# acadam.net
KiCad netlist of a schematic drawn in EAGLE
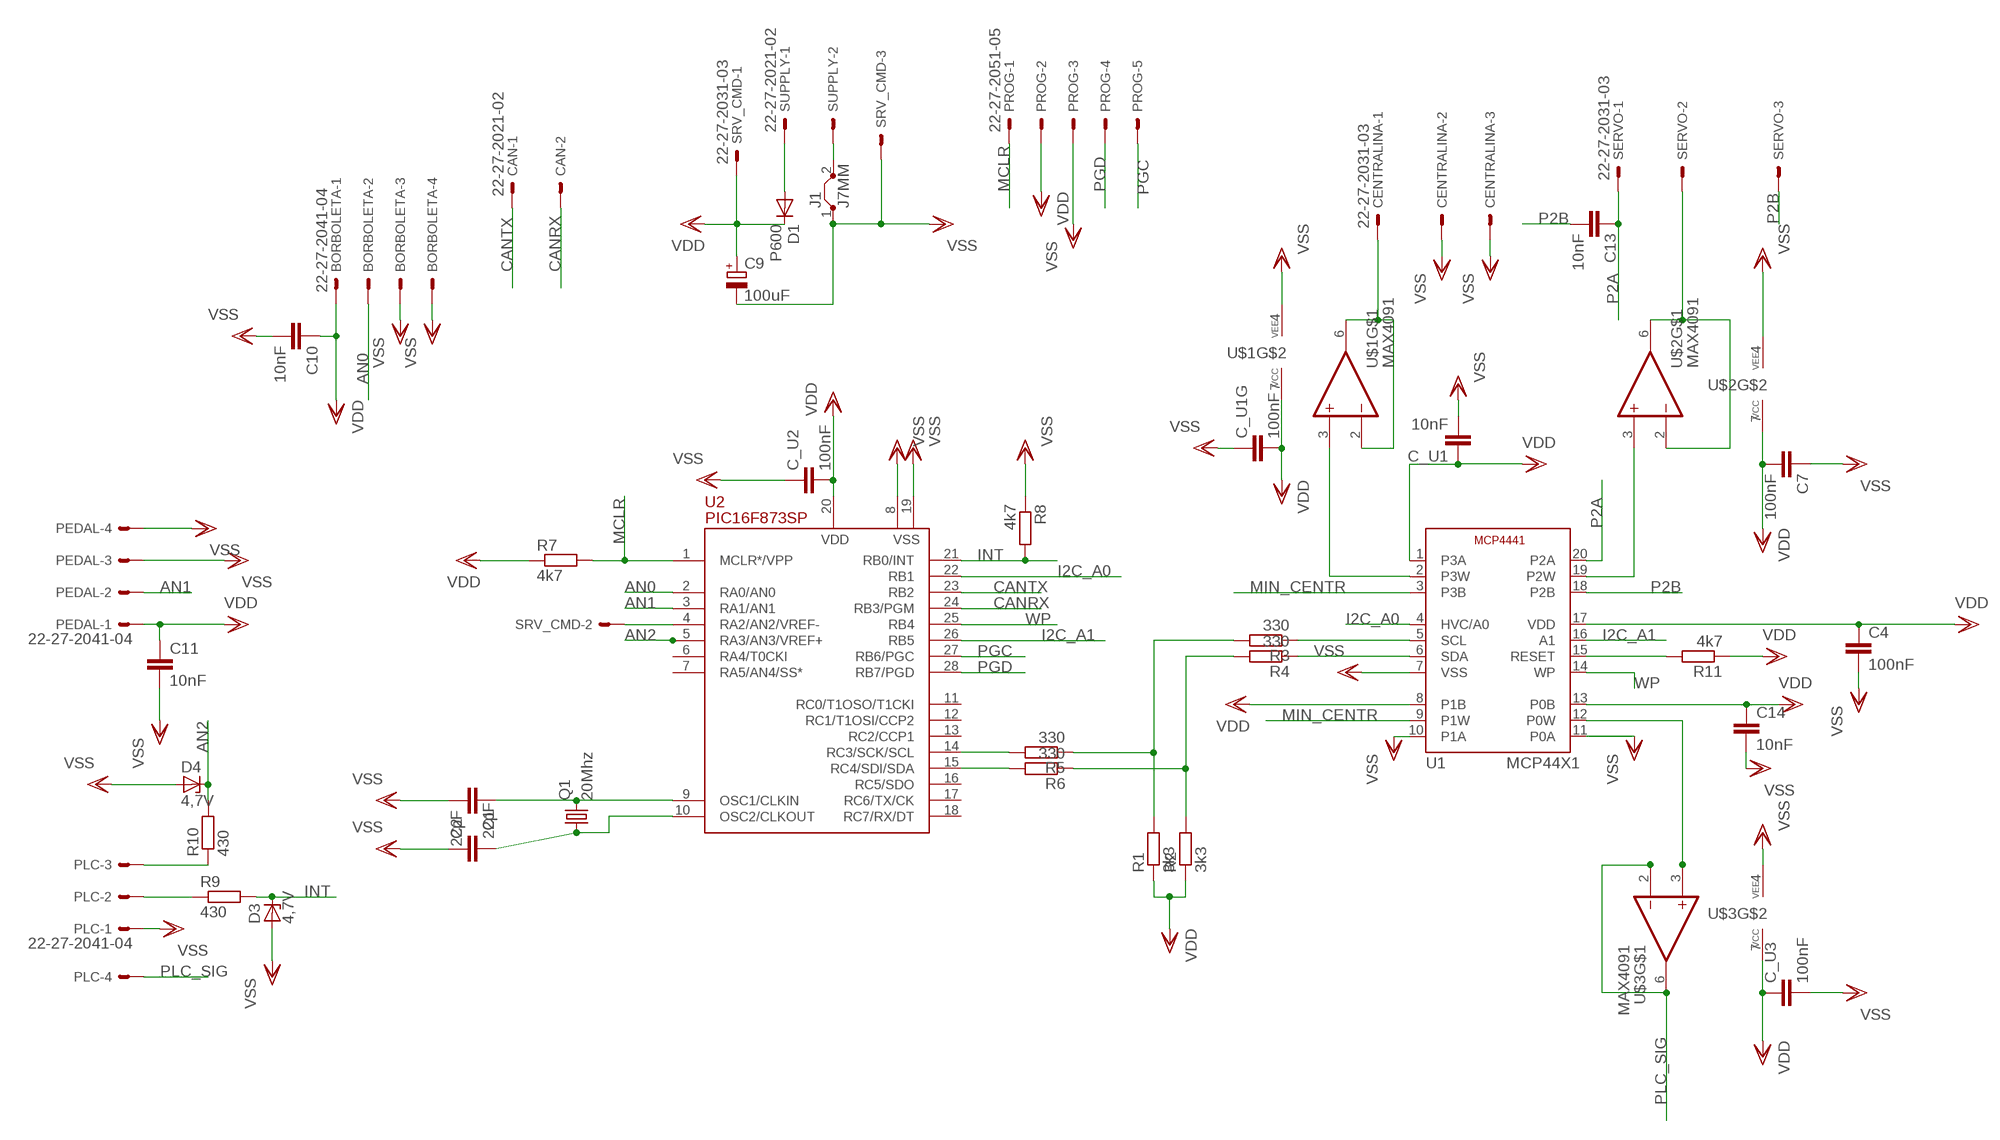
[diagram p0: schematic, sheet 1]

(export (version "E")
  (design (tool "Eeschema 10.0.6"))
  (components
    (comp (ref "BORBOLETA")
      (value "22-27-2041-04")
      (footprint "eagle-import:6410-04")
      (libsource (lib "eagle-import") (part "22-?-0427-2041"))
    )
    (comp (ref "C1")
      (value "22pF")
      (footprint "eagle-import:C0603")
      (libsource (lib "eagle-import") (part "C-EUC0603"))
    )
    (comp (ref "C2")
      (value "22pF")
      (footprint "eagle-import:C0603")
      (libsource (lib "eagle-import") (part "C-EUC0603"))
    )
    (comp (ref "C4")
      (value "100nF")
      (footprint "eagle-import:C0805")
      (libsource (lib "eagle-import") (part "C-EUC0805"))
    )
    (comp (ref "C7")
      (value "100nF")
      (footprint "eagle-import:C0805")
      (libsource (lib "eagle-import") (part "C-EUC0805"))
    )
    (comp (ref "C9")
      (value "100uF")
      (footprint "eagle-import:E2,5-5")
      (libsource (lib "eagle-import") (part "CPOL-EUE2.5-5"))
    )
    (comp (ref "C10")
      (value "10nF")
      (footprint "eagle-import:C0805")
      (libsource (lib "eagle-import") (part "C-EUC0805"))
    )
    (comp (ref "C11")
      (value "10nF")
      (footprint "eagle-import:C0805")
      (libsource (lib "eagle-import") (part "C-EUC0805"))
    )
    (comp (ref "C13")
      (value "10nF")
      (footprint "eagle-import:C0805")
      (libsource (lib "eagle-import") (part "C-EUC0805"))
    )
    (comp (ref "C14")
      (value "10nF")
      (footprint "eagle-import:C0805")
      (libsource (lib "eagle-import") (part "C-EUC0805"))
    )
    (comp (ref "CAN")
      (value "22-27-2021-02")
      (footprint "eagle-import:6410-02")
      (libsource (lib "eagle-import") (part "22-?-0227-2021"))
    )
    (comp (ref "CENTRALINA")
      (value "22-27-2031-03")
      (footprint "eagle-import:6410-03")
      (libsource (lib "eagle-import") (part "22-?-0327-2031"))
    )
    (comp (ref "C_U1")
      (value "10nF")
      (footprint "eagle-import:C0805")
      (libsource (lib "eagle-import") (part "C-EUC0805"))
    )
    (comp (ref "C_U1G")
      (value "100nF")
      (footprint "eagle-import:C0805")
      (libsource (lib "eagle-import") (part "C-EUC0805"))
    )
    (comp (ref "C_U2")
      (value "100nF")
      (footprint "eagle-import:C0805")
      (libsource (lib "eagle-import") (part "C-EUC0805"))
    )
    (comp (ref "C_U3")
      (value "100nF")
      (footprint "eagle-import:C0805")
      (libsource (lib "eagle-import") (part "C-EUC0805"))
    )
    (comp (ref "D1")
      (value "P600")
      (footprint "eagle-import:P6-15")
      (libsource (lib "eagle-import") (part "P600"))
    )
    (comp (ref "D3")
      (value "4,7V")
      (footprint "eagle-import:DO34Z7")
      (libsource (lib "eagle-import") (part "ZENER-DIODEDO34-7"))
    )
    (comp (ref "D4")
      (value "4,7V")
      (footprint "eagle-import:DO34Z7")
      (libsource (lib "eagle-import") (part "ZENER-DIODEDO34-7"))
    )
    (comp (ref "J1")
      (value "J7MM")
      (footprint "eagle-import:07")
      (libsource (lib "eagle-import") (part "J7MM"))
    )
    (comp (ref "PEDAL")
      (value "22-27-2041-04")
      (footprint "eagle-import:6410-04")
      (libsource (lib "eagle-import") (part "22-?-0427-2041"))
    )
    (comp (ref "PLC")
      (value "22-27-2041-04")
      (footprint "eagle-import:6410-04")
      (libsource (lib "eagle-import") (part "22-?-0427-2041"))
    )
    (comp (ref "PROG")
      (value "22-27-2051-05")
      (footprint "eagle-import:6410-05")
      (libsource (lib "eagle-import") (part "22-?-0527-2051"))
    )
    (comp (ref "Q1")
      (value "20Mhz")
      (footprint "eagle-import:HC49_S")
      (libsource (lib "eagle-import") (part "CRYSTALHC49S"))
    )
    (comp (ref "R1")
      (value "3k3")
      (footprint "eagle-import:0204_5")
      (libsource (lib "eagle-import") (part "R-EU_0204/5"))
    )
    (comp (ref "R2")
      (value "3k3")
      (footprint "eagle-import:0204_5")
      (libsource (lib "eagle-import") (part "R-EU_0204/5"))
    )
    (comp (ref "R3")
      (value "330")
      (footprint "eagle-import:0204_5")
      (libsource (lib "eagle-import") (part "R-EU_0204/5"))
    )
    (comp (ref "R4")
      (value "330")
      (footprint "eagle-import:0204_5")
      (libsource (lib "eagle-import") (part "R-EU_0204/5"))
    )
    (comp (ref "R5")
      (value "330")
      (footprint "eagle-import:0204_5")
      (libsource (lib "eagle-import") (part "R-EU_0204/5"))
    )
    (comp (ref "R6")
      (value "330")
      (footprint "eagle-import:0204_5")
      (libsource (lib "eagle-import") (part "R-EU_0204/5"))
    )
    (comp (ref "R7")
      (value "4k7")
      (footprint "eagle-import:0204_5")
      (libsource (lib "eagle-import") (part "R-EU_0204/5"))
    )
    (comp (ref "R8")
      (value "4k7")
      (footprint "eagle-import:0204_5")
      (libsource (lib "eagle-import") (part "R-EU_0204/5"))
    )
    (comp (ref "R9")
      (value "430")
      (footprint "eagle-import:0204_5")
      (libsource (lib "eagle-import") (part "R-EU_0204/5"))
    )
    (comp (ref "R10")
      (value "430")
      (footprint "eagle-import:0204_5")
      (libsource (lib "eagle-import") (part "R-EU_0204/5"))
    )
    (comp (ref "R11")
      (value "4k7")
      (footprint "eagle-import:0204_5")
      (libsource (lib "eagle-import") (part "R-EU_0204/5"))
    )
    (comp (ref "SERVO")
      (value "22-27-2031-03")
      (footprint "eagle-import:6410-03")
      (libsource (lib "eagle-import") (part "22-?-0327-2031"))
    )
    (comp (ref "SRV_CMD")
      (value "22-27-2031-03")
      (footprint "eagle-import:6410-03")
      (libsource (lib "eagle-import") (part "22-?-0327-2031"))
    )
    (comp (ref "SUPPLY")
      (value "22-27-2021-02")
      (footprint "eagle-import:6410-02")
      (libsource (lib "eagle-import") (part "22-?-0227-2021"))
    )
    (comp (ref "U$1")
      (value "MAX4091")
      (footprint "eagle-import:SO-08")
      (libsource (lib "eagle-import") (part "MAX4091"))
    )
    (comp (ref "U$2")
      (value "MAX4091")
      (footprint "eagle-import:SO-08")
      (libsource (lib "eagle-import") (part "MAX4091"))
    )
    (comp (ref "U$3")
      (value "MAX4091")
      (footprint "eagle-import:SO-08")
      (libsource (lib "eagle-import") (part "MAX4091"))
    )
    (comp (ref "U1")
      (value "MCP44X1")
      (footprint "eagle-import:TSSOP20")
      (libsource (lib "eagle-import") (part "MCP44X1"))
    )
    (comp (ref "U2")
      (value "PIC16F873SP")
      (footprint "eagle-import:DIL28-3")
      (libsource (lib "eagle-import") (part "PIC16F873SP"))
    )
  )
  (nets
    (net (code "1") (name "/AN0") (class "Default")
      (node (ref "BORBOLETA") (pin "2") (pinfunction "S_2") (pintype "passive"))
      (node (ref "U2") (pin "2") (pinfunction "RA0/AN0_2") (pintype "bidirectional"))
    )
    (net (code "2") (name "/AN1") (class "Default")
      (node (ref "PEDAL") (pin "2") (pinfunction "S_2") (pintype "passive"))
      (node (ref "U2") (pin "3") (pinfunction "RA1/AN1_3") (pintype "bidirectional"))
    )
    (net (code "3") (name "/AN2") (class "Default")
      (node (ref "D4") (pin "C") (pinfunction "C_C") (pintype "passive"))
      (node (ref "R10") (pin "2") (pinfunction "2_2") (pintype "passive"))
      (node (ref "U2") (pin "5") (pinfunction "RA3/AN3/VREF+_5") (pintype "bidirectional"))
    )
    (net (code "4") (name "/CANRX") (class "Default")
      (node (ref "CAN") (pin "2") (pinfunction "S_2") (pintype "passive"))
      (node (ref "U2") (pin "24") (pinfunction "RB3/PGM_24") (pintype "bidirectional"))
    )
    (net (code "5") (name "/CANTX") (class "Default")
      (node (ref "CAN") (pin "1") (pinfunction "S_1") (pintype "passive"))
      (node (ref "U2") (pin "23") (pinfunction "RB2_23") (pintype "bidirectional"))
    )
    (net (code "6") (name "/I2C_A0") (class "Default")
      (node (ref "U1") (pin "4") (pinfunction "HVC/A0_4") (pintype "bidirectional"))
      (node (ref "U2") (pin "22") (pinfunction "RB1_22") (pintype "bidirectional"))
    )
    (net (code "7") (name "/I2C_A1") (class "Default")
      (node (ref "U1") (pin "16") (pinfunction "A1_16") (pintype "bidirectional"))
      (node (ref "U2") (pin "26") (pinfunction "RB5_26") (pintype "bidirectional"))
    )
    (net (code "8") (name "/INT") (class "Default")
      (node (ref "D3") (pin "C") (pinfunction "C_C") (pintype "passive"))
      (node (ref "R8") (pin "2") (pinfunction "2_2") (pintype "passive"))
      (node (ref "R9") (pin "2") (pinfunction "2_2") (pintype "passive"))
      (node (ref "U2") (pin "21") (pinfunction "RB0/INT_21") (pintype "bidirectional"))
    )
    (net (code "9") (name "/MCLR") (class "Default")
      (node (ref "PROG") (pin "1") (pinfunction "S_1") (pintype "passive"))
      (node (ref "R7") (pin "2") (pinfunction "2_2") (pintype "passive"))
      (node (ref "U2") (pin "1") (pinfunction "MCLR*/VPP_1") (pintype "bidirectional"))
    )
    (net (code "10") (name "/MIN_CENTR") (class "Default")
      (node (ref "U1") (pin "3") (pinfunction "P3B_3") (pintype "bidirectional"))
      (node (ref "U1") (pin "9") (pinfunction "P1W_9") (pintype "bidirectional"))
    )
    (net (code "11") (name "/P2A") (class "Default")
      (node (ref "C13") (pin "1") (pinfunction "1_1") (pintype "passive"))
      (node (ref "SERVO") (pin "1") (pinfunction "S_1") (pintype "passive"))
      (node (ref "U1") (pin "20") (pinfunction "P2A_20") (pintype "bidirectional"))
    )
    (net (code "12") (name "/P2B") (class "Default")
      (node (ref "C13") (pin "2") (pinfunction "2_2") (pintype "passive"))
      (node (ref "SERVO") (pin "3") (pinfunction "S_3") (pintype "passive"))
      (node (ref "U1") (pin "18") (pinfunction "P2B_18") (pintype "bidirectional"))
    )
    (net (code "13") (name "/PGC") (class "Default")
      (node (ref "PROG") (pin "5") (pinfunction "S_5") (pintype "passive"))
      (node (ref "U2") (pin "27") (pinfunction "RB6/PGC_27") (pintype "bidirectional"))
    )
    (net (code "14") (name "/PGD") (class "Default")
      (node (ref "PROG") (pin "4") (pinfunction "S_4") (pintype "passive"))
      (node (ref "U2") (pin "28") (pinfunction "RB7/PGD_28") (pintype "bidirectional"))
    )
    (net (code "15") (name "/PLC_SIG") (class "Default")
      (node (ref "PLC") (pin "4") (pinfunction "S_4") (pintype "passive"))
      (node (ref "U$3") (pin "2") (pinfunction "-IN_2") (pintype "input"))
      (node (ref "U$3") (pin "6") (pinfunction "OUT_6") (pintype "output"))
    )
    (net (code "16") (name "/WP") (class "Default")
      (node (ref "U1") (pin "14") (pinfunction "WP_14") (pintype "bidirectional"))
      (node (ref "U2") (pin "25") (pinfunction "RB4_25") (pintype "bidirectional"))
    )
    (net (code "17") (name "Net-(CENTRALINAA-S)") (class "Default")
      (node (ref "CENTRALINA") (pin "1") (pinfunction "S_1") (pintype "passive"))
      (node (ref "U$1") (pin "2") (pinfunction "-IN_2") (pintype "input"))
      (node (ref "U$1") (pin "6") (pinfunction "OUT_6") (pintype "output"))
    )
    (net (code "18") (name "Net-(PLCB-S)") (class "Default")
      (node (ref "PLC") (pin "2") (pinfunction "S_2") (pintype "passive"))
      (node (ref "R9") (pin "1") (pinfunction "1_1") (pintype "passive"))
    )
    (net (code "19") (name "Net-(PLCC-S)") (class "Default")
      (node (ref "PLC") (pin "3") (pinfunction "S_3") (pintype "passive"))
      (node (ref "R10") (pin "1") (pinfunction "1_1") (pintype "passive"))
    )
    (net (code "20") (name "Net-(R1-Pad2)") (class "Default")
      (node (ref "R1") (pin "2") (pinfunction "2_2") (pintype "passive"))
      (node (ref "R3") (pin "2") (pinfunction "2_2") (pintype "passive"))
      (node (ref "R5") (pin "1") (pinfunction "1_1") (pintype "passive"))
    )
    (net (code "21") (name "Net-(R2-Pad2)") (class "Default")
      (node (ref "R2") (pin "2") (pinfunction "2_2") (pintype "passive"))
      (node (ref "R4") (pin "2") (pinfunction "2_2") (pintype "passive"))
      (node (ref "R6") (pin "1") (pinfunction "1_1") (pintype "passive"))
    )
    (net (code "22") (name "Net-(SERVOB-S)") (class "Default")
      (node (ref "SERVO") (pin "2") (pinfunction "S_2") (pintype "passive"))
      (node (ref "U$2") (pin "2") (pinfunction "-IN_2") (pintype "input"))
      (node (ref "U$2") (pin "6") (pinfunction "OUT_6") (pintype "output"))
    )
    (net (code "23") (name "Net-(SRV_CMDB-S)") (class "Default")
      (node (ref "SRV_CMD") (pin "2") (pinfunction "S_2") (pintype "passive"))
      (node (ref "U2") (pin "4") (pinfunction "RA2/AN2/VREF-_4") (pintype "bidirectional"))
    )
    (net (code "24") (name "Net-(SUPPLYA-S)") (class "Default")
      (node (ref "D1") (pin "A") (pinfunction "A_A") (pintype "passive"))
      (node (ref "SUPPLY") (pin "1") (pinfunction "S_1") (pintype "passive"))
    )
    (net (code "25") (name "Net-(SUPPLYB-S)") (class "Default")
      (node (ref "J1") (pin "2") (pinfunction "2_2") (pintype "passive"))
      (node (ref "SUPPLY") (pin "2") (pinfunction "S_2") (pintype "passive"))
    )
    (net (code "26") (name "Net-(U$1A-+IN)") (class "Default")
      (node (ref "U$1") (pin "3") (pinfunction "+IN_3") (pintype "input"))
      (node (ref "U1") (pin "2") (pinfunction "P3W_2") (pintype "bidirectional"))
    )
    (net (code "27") (name "Net-(U$2A-+IN)") (class "Default")
      (node (ref "U$2") (pin "3") (pinfunction "+IN_3") (pintype "input"))
      (node (ref "U1") (pin "19") (pinfunction "P2W_19") (pintype "bidirectional"))
    )
    (net (code "28") (name "Net-(U$3A-+IN)") (class "Default")
      (node (ref "U$3") (pin "3") (pinfunction "+IN_3") (pintype "input"))
      (node (ref "U1") (pin "12") (pinfunction "P0W_12") (pintype "bidirectional"))
    )
    (net (code "29") (name "Net-(U1-RESET)") (class "Default")
      (node (ref "R11") (pin "2") (pinfunction "2_2") (pintype "passive"))
      (node (ref "U1") (pin "15") (pinfunction "RESET_15") (pintype "bidirectional"))
    )
    (net (code "30") (name "Net-(U1-SCL)") (class "Default")
      (node (ref "R3") (pin "1") (pinfunction "1_1") (pintype "passive"))
      (node (ref "U1") (pin "5") (pinfunction "SCL_5") (pintype "bidirectional"))
    )
    (net (code "31") (name "Net-(U1-SDA)") (class "Default")
      (node (ref "R4") (pin "1") (pinfunction "1_1") (pintype "passive"))
      (node (ref "U1") (pin "6") (pinfunction "SDA_6") (pintype "bidirectional"))
    )
    (net (code "32") (name "Net-(U2-OSC1{slash}CLKIN)") (class "Default")
      (node (ref "C1") (pin "1") (pinfunction "1_1") (pintype "passive"))
      (node (ref "Q1") (pin "2") (pinfunction "2_2") (pintype "passive"))
      (node (ref "U2") (pin "9") (pinfunction "OSC1/CLKIN_9") (pintype "bidirectional"))
    )
    (net (code "33") (name "Net-(U2-OSC2{slash}CLKOUT)") (class "Default")
      (node (ref "C2") (pin "2") (pinfunction "2_2") (pintype "passive"))
      (node (ref "Q1") (pin "1") (pinfunction "1_1") (pintype "passive"))
      (node (ref "U2") (pin "10") (pinfunction "OSC2/CLKOUT_10") (pintype "bidirectional"))
    )
    (net (code "34") (name "Net-(U2-RC3{slash}SCK{slash}SCL)") (class "Default")
      (node (ref "R5") (pin "2") (pinfunction "2_2") (pintype "passive"))
      (node (ref "U2") (pin "14") (pinfunction "RC3/SCK/SCL_14") (pintype "bidirectional"))
    )
    (net (code "35") (name "Net-(U2-RC4{slash}SDI{slash}SDA)") (class "Default")
      (node (ref "R6") (pin "2") (pinfunction "2_2") (pintype "passive"))
      (node (ref "U2") (pin "15") (pinfunction "RC4/SDI/SDA_15") (pintype "bidirectional"))
    )
    (net (code "36") (name "VDD") (class "Default")
      (node (ref "BORBOLETA") (pin "1") (pinfunction "S_1") (pintype "passive"))
      (node (ref "C10") (pin "1") (pinfunction "1_1") (pintype "passive"))
      (node (ref "C11") (pin "1") (pinfunction "1_1") (pintype "passive"))
      (node (ref "C14") (pin "1") (pinfunction "1_1") (pintype "passive"))
      (node (ref "C4") (pin "1") (pinfunction "1_1") (pintype "passive"))
      (node (ref "C7") (pin "2") (pinfunction "2_2") (pintype "passive"))
      (node (ref "C9") (pin "+") (pinfunction "+_+") (pintype "passive"))
      (node (ref "C_U1") (pin "1") (pinfunction "1_1") (pintype "passive"))
      (node (ref "C_U1G") (pin "2") (pinfunction "2_2") (pintype "passive"))
      (node (ref "C_U2") (pin "2") (pinfunction "2_2") (pintype "passive"))
      (node (ref "C_U3") (pin "1") (pinfunction "1_1") (pintype "passive"))
      (node (ref "D1") (pin "C") (pinfunction "C_C") (pintype "passive"))
      (node (ref "PEDAL") (pin "1") (pinfunction "S_1") (pintype "passive"))
      (node (ref "PROG") (pin "2") (pinfunction "S_2") (pintype "passive"))
      (node (ref "R1") (pin "1") (pinfunction "1_1") (pintype "passive"))
      (node (ref "R11") (pin "1") (pinfunction "1_1") (pintype "passive"))
      (node (ref "R2") (pin "1") (pinfunction "1_1") (pintype "passive"))
      (node (ref "R7") (pin "1") (pinfunction "1_1") (pintype "passive"))
      (node (ref "SRV_CMD") (pin "1") (pinfunction "S_1") (pintype "passive"))
      (node (ref "U$1") (pin "7") (pinfunction "VCC_7") (pintype "power_in"))
      (node (ref "U$2") (pin "7") (pinfunction "VCC_7") (pintype "power_in"))
      (node (ref "U$3") (pin "7") (pinfunction "VCC_7") (pintype "power_in"))
      (node (ref "U1") (pin "1") (pinfunction "P3A_1") (pintype "bidirectional"))
      (node (ref "U1") (pin "13") (pinfunction "P0B_13") (pintype "bidirectional"))
      (node (ref "U1") (pin "17") (pinfunction "VDD_17") (pintype "bidirectional"))
      (node (ref "U1") (pin "8") (pinfunction "P1B_8") (pintype "bidirectional"))
      (node (ref "U2") (pin "20") (pinfunction "VDD_20") (pintype "power_in"))
    )
    (net (code "37") (name "VSS") (class "Default")
      (node (ref "BORBOLETA") (pin "3") (pinfunction "S_3") (pintype "passive"))
      (node (ref "BORBOLETA") (pin "4") (pinfunction "S_4") (pintype "passive"))
      (node (ref "C1") (pin "2") (pinfunction "2_2") (pintype "passive"))
      (node (ref "C10") (pin "2") (pinfunction "2_2") (pintype "passive"))
      (node (ref "C11") (pin "2") (pinfunction "2_2") (pintype "passive"))
      (node (ref "C14") (pin "2") (pinfunction "2_2") (pintype "passive"))
      (node (ref "C2") (pin "1") (pinfunction "1_1") (pintype "passive"))
      (node (ref "C4") (pin "2") (pinfunction "2_2") (pintype "passive"))
      (node (ref "C7") (pin "1") (pinfunction "1_1") (pintype "passive"))
      (node (ref "C9") (pin "-") (pinfunction "-_-") (pintype "passive"))
      (node (ref "CENTRALINA") (pin "2") (pinfunction "S_2") (pintype "passive"))
      (node (ref "CENTRALINA") (pin "3") (pinfunction "S_3") (pintype "passive"))
      (node (ref "C_U1") (pin "2") (pinfunction "2_2") (pintype "passive"))
      (node (ref "C_U1G") (pin "1") (pinfunction "1_1") (pintype "passive"))
      (node (ref "C_U2") (pin "1") (pinfunction "1_1") (pintype "passive"))
      (node (ref "C_U3") (pin "2") (pinfunction "2_2") (pintype "passive"))
      (node (ref "D3") (pin "A") (pinfunction "A_A") (pintype "passive"))
      (node (ref "D4") (pin "A") (pinfunction "A_A") (pintype "passive"))
      (node (ref "J1") (pin "1") (pinfunction "1_1") (pintype "passive"))
      (node (ref "PEDAL") (pin "3") (pinfunction "S_3") (pintype "passive"))
      (node (ref "PEDAL") (pin "4") (pinfunction "S_4") (pintype "passive"))
      (node (ref "PLC") (pin "1") (pinfunction "S_1") (pintype "passive"))
      (node (ref "PROG") (pin "3") (pinfunction "S_3") (pintype "passive"))
      (node (ref "R8") (pin "1") (pinfunction "1_1") (pintype "passive"))
      (node (ref "SRV_CMD") (pin "3") (pinfunction "S_3") (pintype "passive"))
      (node (ref "U$1") (pin "4") (pinfunction "VEE_4") (pintype "power_in"))
      (node (ref "U$2") (pin "4") (pinfunction "VEE_4") (pintype "power_in"))
      (node (ref "U$3") (pin "4") (pinfunction "VEE_4") (pintype "power_in"))
      (node (ref "U1") (pin "10") (pinfunction "P1A_10") (pintype "bidirectional"))
      (node (ref "U1") (pin "11") (pinfunction "P0A_11") (pintype "bidirectional"))
      (node (ref "U1") (pin "7") (pinfunction "VSS_7") (pintype "bidirectional"))
      (node (ref "U2") (pin "19") (pinfunction "VSS_19") (pintype "power_in"))
      (node (ref "U2") (pin "8") (pinfunction "VSS_8") (pintype "power_in"))
    )
    (net (code "38") (name "unconnected-(U2-RA4{slash}T0CKI-Pad6)") (class "Default")
      (node (ref "U2") (pin "6") (pinfunction "RA4/T0CKI_6") (pintype "bidirectional"))
    )
    (net (code "39") (name "unconnected-(U2-RA5{slash}AN4{slash}SS*-Pad7)") (class "Default")
      (node (ref "U2") (pin "7") (pinfunction "RA5/AN4/SS*_7") (pintype "bidirectional"))
    )
    (net (code "40") (name "unconnected-(U2-RC0{slash}T1OSO{slash}T1CKI-Pad11)") (class "Default")
      (node (ref "U2") (pin "11") (pinfunction "RC0/T1OSO/T1CKI_11") (pintype "bidirectional"))
    )
    (net (code "41") (name "unconnected-(U2-RC1{slash}T1OSI{slash}CCP2-Pad12)") (class "Default")
      (node (ref "U2") (pin "12") (pinfunction "RC1/T1OSI/CCP2_12") (pintype "bidirectional"))
    )
    (net (code "42") (name "unconnected-(U2-RC2{slash}CCP1-Pad13)") (class "Default")
      (node (ref "U2") (pin "13") (pinfunction "RC2/CCP1_13") (pintype "bidirectional"))
    )
    (net (code "43") (name "unconnected-(U2-RC5{slash}SDO-Pad16)") (class "Default")
      (node (ref "U2") (pin "16") (pinfunction "RC5/SDO_16") (pintype "bidirectional"))
    )
    (net (code "44") (name "unconnected-(U2-RC6{slash}TX{slash}CK-Pad17)") (class "Default")
      (node (ref "U2") (pin "17") (pinfunction "RC6/TX/CK_17") (pintype "bidirectional"))
    )
    (net (code "45") (name "unconnected-(U2-RC7{slash}RX{slash}DT-Pad18)") (class "Default")
      (node (ref "U2") (pin "18") (pinfunction "RC7/RX/DT_18") (pintype "bidirectional"))
    )
  )
)
